# Controller_V0_2.net
KiCad netlist of a schematic drawn in EAGLE
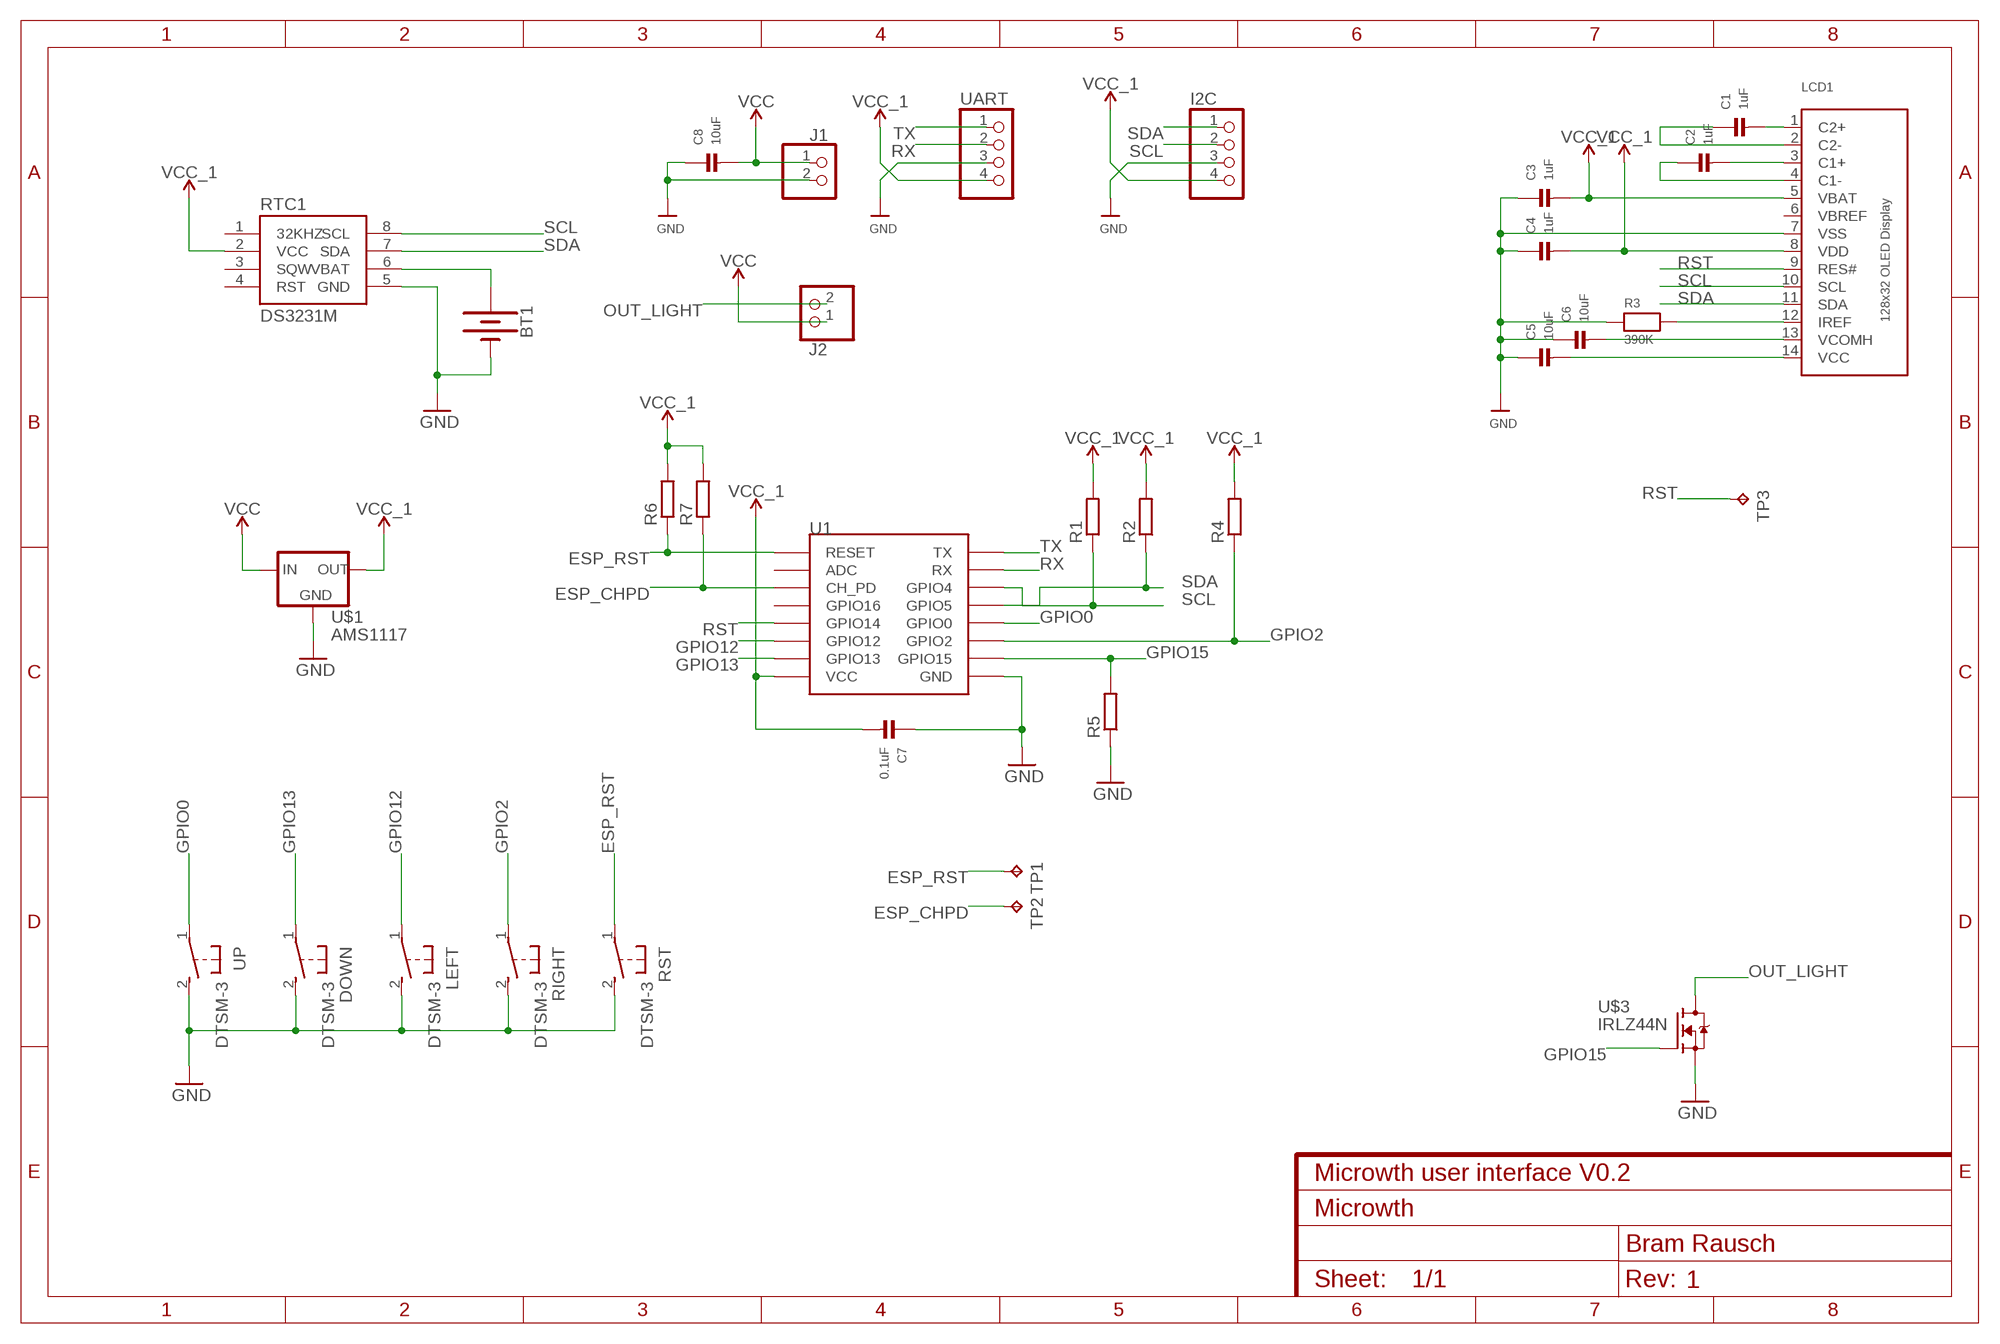
[diagram p0: schematic, sheet 1]

(export (version "E")
  (design (tool "Eeschema 10.0.6"))
  (components
    (comp (ref "BT1")
      (value "BATTERY-20MM_PTH")
      (footprint "eagle-import:BATTCOM_20MM_PTH")
      (libsource (lib "eagle-import") (part "BATTERY-20MM_PTH"))
    )
    (comp (ref "C1")
      (value "1uF")
      (footprint "eagle-import:0805")
      (libsource (lib "eagle-import") (part "CAP_CERAMIC0805"))
    )
    (comp (ref "C2")
      (value "1uF")
      (footprint "eagle-import:0805")
      (libsource (lib "eagle-import") (part "CAP_CERAMIC0805"))
    )
    (comp (ref "C3")
      (value "1uF")
      (footprint "eagle-import:0805")
      (libsource (lib "eagle-import") (part "CAP_CERAMIC0805"))
    )
    (comp (ref "C4")
      (value "1uF")
      (footprint "eagle-import:0805")
      (libsource (lib "eagle-import") (part "CAP_CERAMIC0805"))
    )
    (comp (ref "C5")
      (value "10uF")
      (footprint "eagle-import:0805")
      (libsource (lib "eagle-import") (part "CAP_CERAMIC0805"))
    )
    (comp (ref "C6")
      (value "10uF")
      (footprint "eagle-import:0805")
      (libsource (lib "eagle-import") (part "CAP_CERAMIC0805"))
    )
    (comp (ref "C7")
      (value "0.1uF")
      (footprint "eagle-import:0805")
      (libsource (lib "eagle-import") (part "CAP_CERAMIC0805"))
    )
    (comp (ref "C8")
      (value "10uF")
      (footprint "eagle-import:0805")
      (libsource (lib "eagle-import") (part "CAP_CERAMIC0805"))
    )
    (comp (ref "DOWN")
      (value "DTSM-3")
      (footprint "eagle-import:DTSM-3")
      (libsource (lib "eagle-import") (part "DTSM-3"))
    )
    (comp (ref "I2C")
      (value "PINHD-1X4")
      (footprint "eagle-import:1X04")
      (libsource (lib "eagle-import") (part "PINHD-1X4"))
    )
    (comp (ref "J1")
      (value "PINHD-1X2")
      (footprint "eagle-import:1X02")
      (libsource (lib "eagle-import") (part "PINHD-1X2"))
    )
    (comp (ref "J2")
      (value "PINHD-1X2")
      (footprint "eagle-import:1X02")
      (libsource (lib "eagle-import") (part "PINHD-1X2"))
    )
    (comp (ref "LCD1")
      (value "DISP_OLED_UG-2832HSWEG02")
      (footprint "eagle-import:UG-2832HSWEG02_WRAPUNDER")
      (libsource (lib "eagle-import") (part "DISP_OLED_UG-2832HSWEG02"))
    )
    (comp (ref "LEFT")
      (value "DTSM-3")
      (footprint "eagle-import:DTSM-3")
      (libsource (lib "eagle-import") (part "DTSM-3"))
    )
    (comp (ref "R1")
      (value "R-EU_R0805")
      (footprint "eagle-import:R0805")
      (libsource (lib "eagle-import") (part "R-EU_R0805"))
    )
    (comp (ref "R2")
      (value "R-EU_R0805")
      (footprint "eagle-import:R0805")
      (libsource (lib "eagle-import") (part "R-EU_R0805"))
    )
    (comp (ref "R3")
      (value "390K")
      (footprint "eagle-import:0805")
      (libsource (lib "eagle-import") (part "RESISTOR0805"))
    )
    (comp (ref "R4")
      (value "R-EU_R0805")
      (footprint "eagle-import:R0805")
      (libsource (lib "eagle-import") (part "R-EU_R0805"))
    )
    (comp (ref "R5")
      (value "R-EU_R0805")
      (footprint "eagle-import:R0805")
      (libsource (lib "eagle-import") (part "R-EU_R0805"))
    )
    (comp (ref "R6")
      (value "R-EU_R0805")
      (footprint "eagle-import:R0805")
      (libsource (lib "eagle-import") (part "R-EU_R0805"))
    )
    (comp (ref "R7")
      (value "R-EU_R0805")
      (footprint "eagle-import:R0805")
      (libsource (lib "eagle-import") (part "R-EU_R0805"))
    )
    (comp (ref "RIGHT")
      (value "DTSM-3")
      (footprint "eagle-import:DTSM-3")
      (libsource (lib "eagle-import") (part "DTSM-3"))
    )
    (comp (ref "RST")
      (value "DTSM-3")
      (footprint "eagle-import:DTSM-3")
      (libsource (lib "eagle-import") (part "DTSM-3"))
    )
    (comp (ref "RTC1")
      (value "DS3231M")
      (footprint "eagle-import:SO08")
      (libsource (lib "eagle-import") (part "DS3231M"))
    )
    (comp (ref "TP1")
      (value "TPB1,27")
      (footprint "eagle-import:B1,27")
      (libsource (lib "eagle-import") (part "TPB1,27"))
    )
    (comp (ref "TP2")
      (value "TPB1,27")
      (footprint "eagle-import:B1,27")
      (libsource (lib "eagle-import") (part "TPB1,27"))
    )
    (comp (ref "TP3")
      (value "TPB1,27")
      (footprint "eagle-import:B1,27")
      (libsource (lib "eagle-import") (part "TPB1,27"))
    )
    (comp (ref "U$1")
      (value "AMS1117")
      (footprint "eagle-import:SOT223")
      (libsource (lib "eagle-import") (part "AMS1117"))
    )
    (comp (ref "U$3")
      (value "IRLZ44N")
      (footprint "eagle-import:TO220")
      (libsource (lib "eagle-import") (part "IRLZ44N"))
    )
    (comp (ref "U1")
      (value "ESP12SMD")
      (footprint "eagle-import:ESP12-SMD")
      (libsource (lib "eagle-import") (part "ESP12SMD"))
    )
    (comp (ref "UART")
      (value "PINHD-1X4")
      (footprint "eagle-import:1X04")
      (libsource (lib "eagle-import") (part "PINHD-1X4"))
    )
    (comp (ref "UP")
      (value "DTSM-3")
      (footprint "eagle-import:DTSM-3")
      (libsource (lib "eagle-import") (part "DTSM-3"))
    )
  )
  (nets
    (net (code "1") (name "/ESP_CHPD") (class "Default")
      (node (ref "R7") (pin "1") (pinfunction "1_1") (pintype "passive"))
      (node (ref "TP2") (pin "TP") (pinfunction "TP_TP") (pintype "input"))
      (node (ref "U1") (pin "CH_PD") (pinfunction "CH_PD_CH_PD") (pintype "bidirectional"))
    )
    (net (code "2") (name "/ESP_RST") (class "Default")
      (node (ref "R6") (pin "1") (pinfunction "1_1") (pintype "passive"))
      (node (ref "RST") (pin "1") (pinfunction "1_1") (pintype "passive"))
      (node (ref "TP1") (pin "TP") (pinfunction "TP_TP") (pintype "input"))
      (node (ref "U1") (pin "RESET") (pinfunction "RESET_RESET") (pintype "bidirectional"))
    )
    (net (code "3") (name "/GPIO0") (class "Default")
      (node (ref "U1") (pin "GPIO0") (pinfunction "GPIO0_GPIO0") (pintype "bidirectional"))
      (node (ref "UP") (pin "1") (pinfunction "1_1") (pintype "passive"))
    )
    (net (code "4") (name "/GPIO2") (class "Default")
      (node (ref "R4") (pin "1") (pinfunction "1_1") (pintype "passive"))
      (node (ref "RIGHT") (pin "1") (pinfunction "1_1") (pintype "passive"))
      (node (ref "U1") (pin "GPIO2") (pinfunction "GPIO2_GPIO2") (pintype "bidirectional"))
    )
    (net (code "5") (name "/GPIO12") (class "Default")
      (node (ref "LEFT") (pin "1") (pinfunction "1_1") (pintype "passive"))
      (node (ref "U1") (pin "GPIO12") (pinfunction "GPIO12_GPIO12") (pintype "bidirectional"))
    )
    (net (code "6") (name "/GPIO13") (class "Default")
      (node (ref "DOWN") (pin "1") (pinfunction "1_1") (pintype "passive"))
      (node (ref "U1") (pin "GPIO13") (pinfunction "GPIO13_GPIO13") (pintype "bidirectional"))
    )
    (net (code "7") (name "/GPIO15") (class "Default")
      (node (ref "R5") (pin "2") (pinfunction "2_2") (pintype "passive"))
      (node (ref "U$3") (pin "1") (pinfunction "G_1") (pintype "passive"))
      (node (ref "U1") (pin "GPIO15") (pinfunction "GPIO15_GPIO15") (pintype "bidirectional"))
    )
    (net (code "8") (name "/OUT_LIGHT") (class "Default")
      (node (ref "J2") (pin "2") (pinfunction "2_2") (pintype "passive"))
      (node (ref "U$3") (pin "2") (pinfunction "D_2") (pintype "passive"))
    )
    (net (code "9") (name "/RST") (class "Default")
      (node (ref "LCD1") (pin "9") (pinfunction "RES#_9") (pintype "bidirectional"))
      (node (ref "TP3") (pin "TP") (pinfunction "TP_TP") (pintype "input"))
      (node (ref "U1") (pin "GPIO14") (pinfunction "GPIO14_GPIO14") (pintype "bidirectional"))
    )
    (net (code "10") (name "/RX") (class "Default")
      (node (ref "U1") (pin "RXD0") (pinfunction "RX_RXD0") (pintype "bidirectional"))
      (node (ref "UART") (pin "2") (pinfunction "2_2") (pintype "passive"))
    )
    (net (code "11") (name "/SCL") (class "Default")
      (node (ref "I2C") (pin "2") (pinfunction "2_2") (pintype "passive"))
      (node (ref "LCD1") (pin "10") (pinfunction "SCL_10") (pintype "bidirectional"))
      (node (ref "R1") (pin "1") (pinfunction "1_1") (pintype "passive"))
      (node (ref "RTC1") (pin "8") (pinfunction "SCL_8") (pintype "bidirectional"))
      (node (ref "U1") (pin "GPIO4") (pinfunction "GPIO4_GPIO4") (pintype "bidirectional"))
    )
    (net (code "12") (name "/SDA") (class "Default")
      (node (ref "I2C") (pin "1") (pinfunction "1_1") (pintype "passive"))
      (node (ref "LCD1") (pin "11") (pinfunction "SDA_11") (pintype "bidirectional"))
      (node (ref "R2") (pin "1") (pinfunction "1_1") (pintype "passive"))
      (node (ref "RTC1") (pin "7") (pinfunction "SDA_7") (pintype "bidirectional"))
      (node (ref "U1") (pin "GPIO5") (pinfunction "GPIO5_GPIO5") (pintype "bidirectional"))
    )
    (net (code "13") (name "/TX") (class "Default")
      (node (ref "U1") (pin "TXD0") (pinfunction "TX_TXD0") (pintype "bidirectional"))
      (node (ref "UART") (pin "1") (pinfunction "1_1") (pintype "passive"))
    )
    (net (code "14") (name "/VBREF") (class "Default")
      (node (ref "LCD1") (pin "6") (pinfunction "VBREF_6") (pintype "power_in"))
    )
    (net (code "15") (name "GND") (class "Default")
      (node (ref "BT1") (pin "2") (pinfunction "-_2") (pintype "power_in"))
      (node (ref "C3") (pin "1") (pinfunction "P$1_1") (pintype "passive"))
      (node (ref "C4") (pin "1") (pinfunction "P$1_1") (pintype "passive"))
      (node (ref "C5") (pin "1") (pinfunction "P$1_1") (pintype "passive"))
      (node (ref "C6") (pin "1") (pinfunction "P$1_1") (pintype "passive"))
      (node (ref "C7") (pin "1") (pinfunction "P$1_1") (pintype "passive"))
      (node (ref "C8") (pin "1") (pinfunction "P$1_1") (pintype "passive"))
      (node (ref "DOWN") (pin "2") (pinfunction "2_2") (pintype "passive"))
      (node (ref "I2C") (pin "3") (pinfunction "3_3") (pintype "passive"))
      (node (ref "J1") (pin "2") (pinfunction "2_2") (pintype "passive"))
      (node (ref "LCD1") (pin "7") (pinfunction "VSS_7") (pintype "power_in"))
      (node (ref "LEFT") (pin "2") (pinfunction "2_2") (pintype "passive"))
      (node (ref "R3") (pin "1") (pinfunction "1_1") (pintype "passive"))
      (node (ref "R5") (pin "1") (pinfunction "1_1") (pintype "passive"))
      (node (ref "RIGHT") (pin "2") (pinfunction "2_2") (pintype "passive"))
      (node (ref "RST") (pin "2") (pinfunction "2_2") (pintype "passive"))
      (node (ref "RTC1") (pin "5") (pinfunction "GND_5") (pintype "power_in"))
      (node (ref "U$1") (pin "1") (pinfunction "GND_1") (pintype "input"))
      (node (ref "U$3") (pin "3") (pinfunction "S_3") (pintype "passive"))
      (node (ref "U1") (pin "GND") (pinfunction "GND_GND") (pintype "bidirectional"))
      (node (ref "UART") (pin "3") (pinfunction "3_3") (pintype "passive"))
      (node (ref "UP") (pin "2") (pinfunction "2_2") (pintype "passive"))
    )
    (net (code "16") (name "Net-(BT1-+)") (class "Default")
      (node (ref "BT1") (pin "1") (pinfunction "+_1") (pintype "power_in"))
      (node (ref "RTC1") (pin "6") (pinfunction "VBAT_6") (pintype "power_in"))
    )
    (net (code "17") (name "Net-(C1-P$1)") (class "Default")
      (node (ref "C1") (pin "1") (pinfunction "P$1_1") (pintype "passive"))
      (node (ref "LCD1") (pin "2") (pinfunction "C2-_2") (pintype "bidirectional"))
    )
    (net (code "18") (name "Net-(C1-P$2)") (class "Default")
      (node (ref "C1") (pin "2") (pinfunction "P$2_2") (pintype "passive"))
      (node (ref "LCD1") (pin "1") (pinfunction "C2+_1") (pintype "bidirectional"))
    )
    (net (code "19") (name "Net-(C2-P$1)") (class "Default")
      (node (ref "C2") (pin "1") (pinfunction "P$1_1") (pintype "passive"))
      (node (ref "LCD1") (pin "4") (pinfunction "C1-_4") (pintype "bidirectional"))
    )
    (net (code "20") (name "Net-(C2-P$2)") (class "Default")
      (node (ref "C2") (pin "2") (pinfunction "P$2_2") (pintype "passive"))
      (node (ref "LCD1") (pin "3") (pinfunction "C1+_3") (pintype "bidirectional"))
    )
    (net (code "21") (name "Net-(C5-P$2)") (class "Default")
      (node (ref "C5") (pin "2") (pinfunction "P$2_2") (pintype "passive"))
      (node (ref "LCD1") (pin "14") (pinfunction "VCC_14") (pintype "power_in"))
    )
    (net (code "22") (name "Net-(C6-P$2)") (class "Default")
      (node (ref "C6") (pin "2") (pinfunction "P$2_2") (pintype "passive"))
      (node (ref "LCD1") (pin "13") (pinfunction "VCOMH_13") (pintype "power_in"))
    )
    (net (code "23") (name "Net-(LCD1-IREF)") (class "Default")
      (node (ref "LCD1") (pin "12") (pinfunction "IREF_12") (pintype "bidirectional"))
      (node (ref "R3") (pin "2") (pinfunction "2_2") (pintype "passive"))
    )
    (net (code "24") (name "VCC") (class "Default")
      (node (ref "C8") (pin "2") (pinfunction "P$2_2") (pintype "passive"))
      (node (ref "J1") (pin "1") (pinfunction "1_1") (pintype "passive"))
      (node (ref "J2") (pin "1") (pinfunction "1_1") (pintype "passive"))
      (node (ref "U$1") (pin "3") (pinfunction "IN_3") (pintype "input"))
    )
    (net (code "25") (name "VCC_1") (class "Default")
      (node (ref "C3") (pin "2") (pinfunction "P$2_2") (pintype "passive"))
      (node (ref "C4") (pin "2") (pinfunction "P$2_2") (pintype "passive"))
      (node (ref "C7") (pin "2") (pinfunction "P$2_2") (pintype "passive"))
      (node (ref "I2C") (pin "4") (pinfunction "4_4") (pintype "passive"))
      (node (ref "LCD1") (pin "5") (pinfunction "VBAT_5") (pintype "power_in"))
      (node (ref "LCD1") (pin "8") (pinfunction "VDD_8") (pintype "power_in"))
      (node (ref "R1") (pin "2") (pinfunction "2_2") (pintype "passive"))
      (node (ref "R2") (pin "2") (pinfunction "2_2") (pintype "passive"))
      (node (ref "R4") (pin "2") (pinfunction "2_2") (pintype "passive"))
      (node (ref "R6") (pin "2") (pinfunction "2_2") (pintype "passive"))
      (node (ref "R7") (pin "2") (pinfunction "2_2") (pintype "passive"))
      (node (ref "RTC1") (pin "2") (pinfunction "VCC_2") (pintype "power_in"))
      (node (ref "U$1") (pin "2") (pinfunction "OUT_2") (pintype "passive"))
      (node (ref "U1") (pin "VCC") (pinfunction "VCC_VCC") (pintype "bidirectional"))
      (node (ref "UART") (pin "4") (pinfunction "4_4") (pintype "passive"))
    )
    (net (code "26") (name "unconnected-(RTC1-32KHZ-Pad1)") (class "Default")
      (node (ref "RTC1") (pin "1") (pinfunction "32KHZ_1") (pintype "output"))
    )
    (net (code "27") (name "unconnected-(RTC1-RST-Pad4)") (class "Default")
      (node (ref "RTC1") (pin "4") (pinfunction "RST_4") (pintype "bidirectional"))
    )
    (net (code "28") (name "unconnected-(RTC1-SQW-Pad3)") (class "Default")
      (node (ref "RTC1") (pin "3") (pinfunction "SQW_3") (pintype "output"))
    )
    (net (code "29") (name "unconnected-(U1-PadADC)") (class "Default")
      (node (ref "U1") (pin "ADC") (pinfunction "ADC_ADC") (pintype "bidirectional"))
    )
    (net (code "30") (name "unconnected-(U1-PadGPIO16)") (class "Default")
      (node (ref "U1") (pin "GPIO16") (pinfunction "GPIO16_GPIO16") (pintype "bidirectional"))
    )
  )
)
